# led.net
KiCad netlist of a schematic drawn in Altium Designer
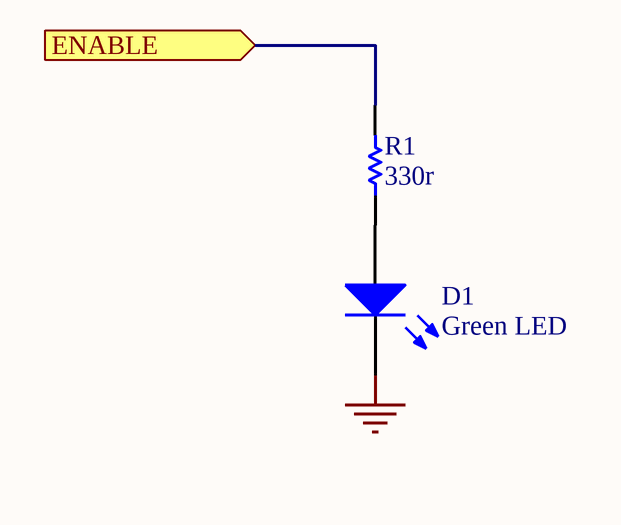
[diagram p0: led.SchDoc]

(export (version "E")
  (design (tool "Eeschema 10.0.6"))
  (components
    (comp (ref "D1")
      (value "Green LED")
      (footprint "LED 0805")
      (description "Typical INFRARED GaAs LED")
      (fields (field (name "PUBLISHER") "Altium Limited"))
      (libsource (lib "Miscellaneous Devices") (part "LED0"))
    )
    (comp (ref "R1")
      (value "330r")
      (footprint "RESC1608N")
      (description "Resistor")
      (fields (field (name "PUBLISHER") "Altium Limited"))
      (libsource (lib "Miscellaneous Devices") (part "Res1"))
    )
  )
  (nets
    (net (code "1") (name "/ENABLE") (class "Default")
      (node (ref "R1") (pin "2") (pinfunction "2_2") (pintype "passive"))
    )
    (net (code "2") (name "GND") (class "Default")
      (node (ref "D1") (pin "2") (pinfunction "K_2") (pintype "passive"))
    )
    (net (code "3") (name "Net-(D1-A)") (class "Default")
      (node (ref "D1") (pin "1") (pinfunction "A_1") (pintype "passive"))
      (node (ref "R1") (pin "1") (pinfunction "1_1") (pintype "passive"))
    )
  )
)
